# untitled.net
KiCad netlist of a schematic drawn in EAGLE
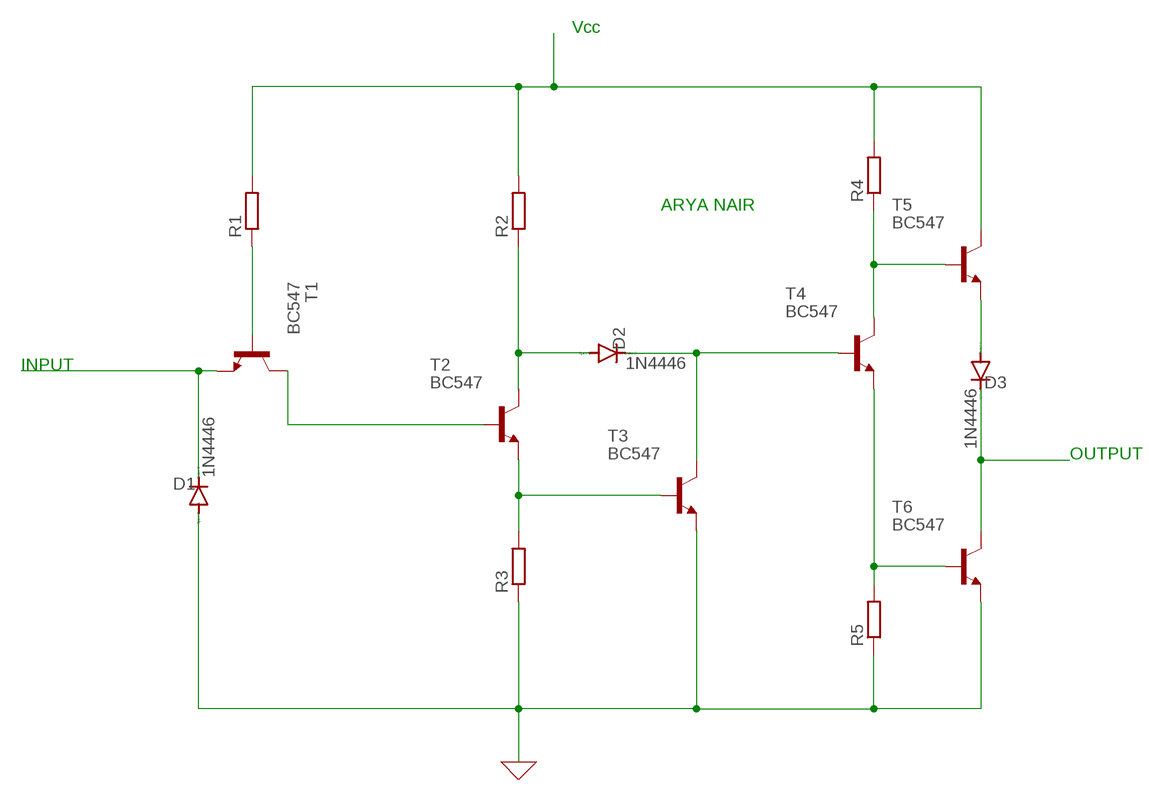
[diagram p0: schematic, sheet 1]

(export (version "E")
  (design (tool "Eeschema 10.0.6"))
  (components
    (comp (ref "D1")
      (value "1N4446")
      (footprint "eagle-import:DO35-10")
      (libsource (lib "eagle-import") (part "1N4446"))
    )
    (comp (ref "D2")
      (value "1N4446")
      (footprint "eagle-import:DO35-10")
      (libsource (lib "eagle-import") (part "1N4446"))
    )
    (comp (ref "D3")
      (value "1N4446")
      (footprint "eagle-import:DO35-10")
      (libsource (lib "eagle-import") (part "1N4446"))
    )
    (comp (ref "R1")
      (value "R-EU_0204/2V")
      (footprint "eagle-import:0204V")
      (libsource (lib "eagle-import") (part "R-EU_0204/2V"))
    )
    (comp (ref "R2")
      (value "R-EU_0204/2V")
      (footprint "eagle-import:0204V")
      (libsource (lib "eagle-import") (part "R-EU_0204/2V"))
    )
    (comp (ref "R3")
      (value "R-EU_0204/2V")
      (footprint "eagle-import:0204V")
      (libsource (lib "eagle-import") (part "R-EU_0204/2V"))
    )
    (comp (ref "R4")
      (value "R-EU_0204/2V")
      (footprint "eagle-import:0204V")
      (libsource (lib "eagle-import") (part "R-EU_0204/2V"))
    )
    (comp (ref "R5")
      (value "R-EU_0204/2V")
      (footprint "eagle-import:0204V")
      (libsource (lib "eagle-import") (part "R-EU_0204/2V"))
    )
    (comp (ref "T1")
      (value "BC547")
      (footprint "eagle-import:TO92")
      (libsource (lib "eagle-import") (part "BC547"))
    )
    (comp (ref "T2")
      (value "BC547")
      (footprint "eagle-import:TO92")
      (libsource (lib "eagle-import") (part "BC547"))
    )
    (comp (ref "T3")
      (value "BC547")
      (footprint "eagle-import:TO92")
      (libsource (lib "eagle-import") (part "BC547"))
    )
    (comp (ref "T4")
      (value "BC547")
      (footprint "eagle-import:TO92")
      (libsource (lib "eagle-import") (part "BC547"))
    )
    (comp (ref "T5")
      (value "BC547")
      (footprint "eagle-import:TO92")
      (libsource (lib "eagle-import") (part "BC547"))
    )
    (comp (ref "T6")
      (value "BC547")
      (footprint "eagle-import:TO92")
      (libsource (lib "eagle-import") (part "BC547"))
    )
  )
  (nets
    (net (code "1") (name "GND") (class "Default")
      (node (ref "D1") (pin "A") (pinfunction "A_A") (pintype "passive"))
      (node (ref "R3") (pin "1") (pinfunction "1_1") (pintype "passive"))
      (node (ref "R5") (pin "1") (pinfunction "1_1") (pintype "passive"))
      (node (ref "T3") (pin "1") (pinfunction "E_1") (pintype "passive"))
      (node (ref "T6") (pin "1") (pinfunction "E_1") (pintype "passive"))
    )
    (net (code "2") (name "Net-(T1-B)") (class "Default")
      (node (ref "R1") (pin "1") (pinfunction "1_1") (pintype "passive"))
      (node (ref "T1") (pin "2") (pinfunction "B_2") (pintype "passive"))
    )
    (net (code "3") (name "Net-(T1-C)") (class "Default")
      (node (ref "T1") (pin "3") (pinfunction "C_3") (pintype "passive"))
      (node (ref "T2") (pin "2") (pinfunction "B_2") (pintype "passive"))
    )
    (net (code "4") (name "Net-(T1-E)") (class "Default")
      (node (ref "D1") (pin "C") (pinfunction "C_C") (pintype "passive"))
      (node (ref "T1") (pin "1") (pinfunction "E_1") (pintype "passive"))
    )
    (net (code "5") (name "Net-(T2-C)") (class "Default")
      (node (ref "D2") (pin "A") (pinfunction "A_A") (pintype "passive"))
      (node (ref "R2") (pin "1") (pinfunction "1_1") (pintype "passive"))
      (node (ref "T2") (pin "3") (pinfunction "C_3") (pintype "passive"))
    )
    (net (code "6") (name "Net-(T2-E)") (class "Default")
      (node (ref "R3") (pin "2") (pinfunction "2_2") (pintype "passive"))
      (node (ref "T2") (pin "1") (pinfunction "E_1") (pintype "passive"))
      (node (ref "T3") (pin "2") (pinfunction "B_2") (pintype "passive"))
    )
    (net (code "7") (name "Net-(T3-C)") (class "Default")
      (node (ref "D2") (pin "C") (pinfunction "C_C") (pintype "passive"))
      (node (ref "T3") (pin "3") (pinfunction "C_3") (pintype "passive"))
      (node (ref "T4") (pin "2") (pinfunction "B_2") (pintype "passive"))
    )
    (net (code "8") (name "Net-(T4-C)") (class "Default")
      (node (ref "R4") (pin "1") (pinfunction "1_1") (pintype "passive"))
      (node (ref "T4") (pin "3") (pinfunction "C_3") (pintype "passive"))
      (node (ref "T5") (pin "2") (pinfunction "B_2") (pintype "passive"))
    )
    (net (code "9") (name "Net-(T4-E)") (class "Default")
      (node (ref "R5") (pin "2") (pinfunction "2_2") (pintype "passive"))
      (node (ref "T4") (pin "1") (pinfunction "E_1") (pintype "passive"))
      (node (ref "T6") (pin "2") (pinfunction "B_2") (pintype "passive"))
    )
    (net (code "10") (name "Net-(T5-C)") (class "Default")
      (node (ref "R1") (pin "2") (pinfunction "2_2") (pintype "passive"))
      (node (ref "R2") (pin "2") (pinfunction "2_2") (pintype "passive"))
      (node (ref "R4") (pin "2") (pinfunction "2_2") (pintype "passive"))
      (node (ref "T5") (pin "3") (pinfunction "C_3") (pintype "passive"))
    )
    (net (code "11") (name "Net-(T5-E)") (class "Default")
      (node (ref "D3") (pin "A") (pinfunction "A_A") (pintype "passive"))
      (node (ref "T5") (pin "1") (pinfunction "E_1") (pintype "passive"))
    )
    (net (code "12") (name "Net-(T6-C)") (class "Default")
      (node (ref "D3") (pin "C") (pinfunction "C_C") (pintype "passive"))
      (node (ref "T6") (pin "3") (pinfunction "C_3") (pintype "passive"))
    )
  )
)
